# octanis_v0_1.net
KiCad netlist of a schematic drawn in EAGLE
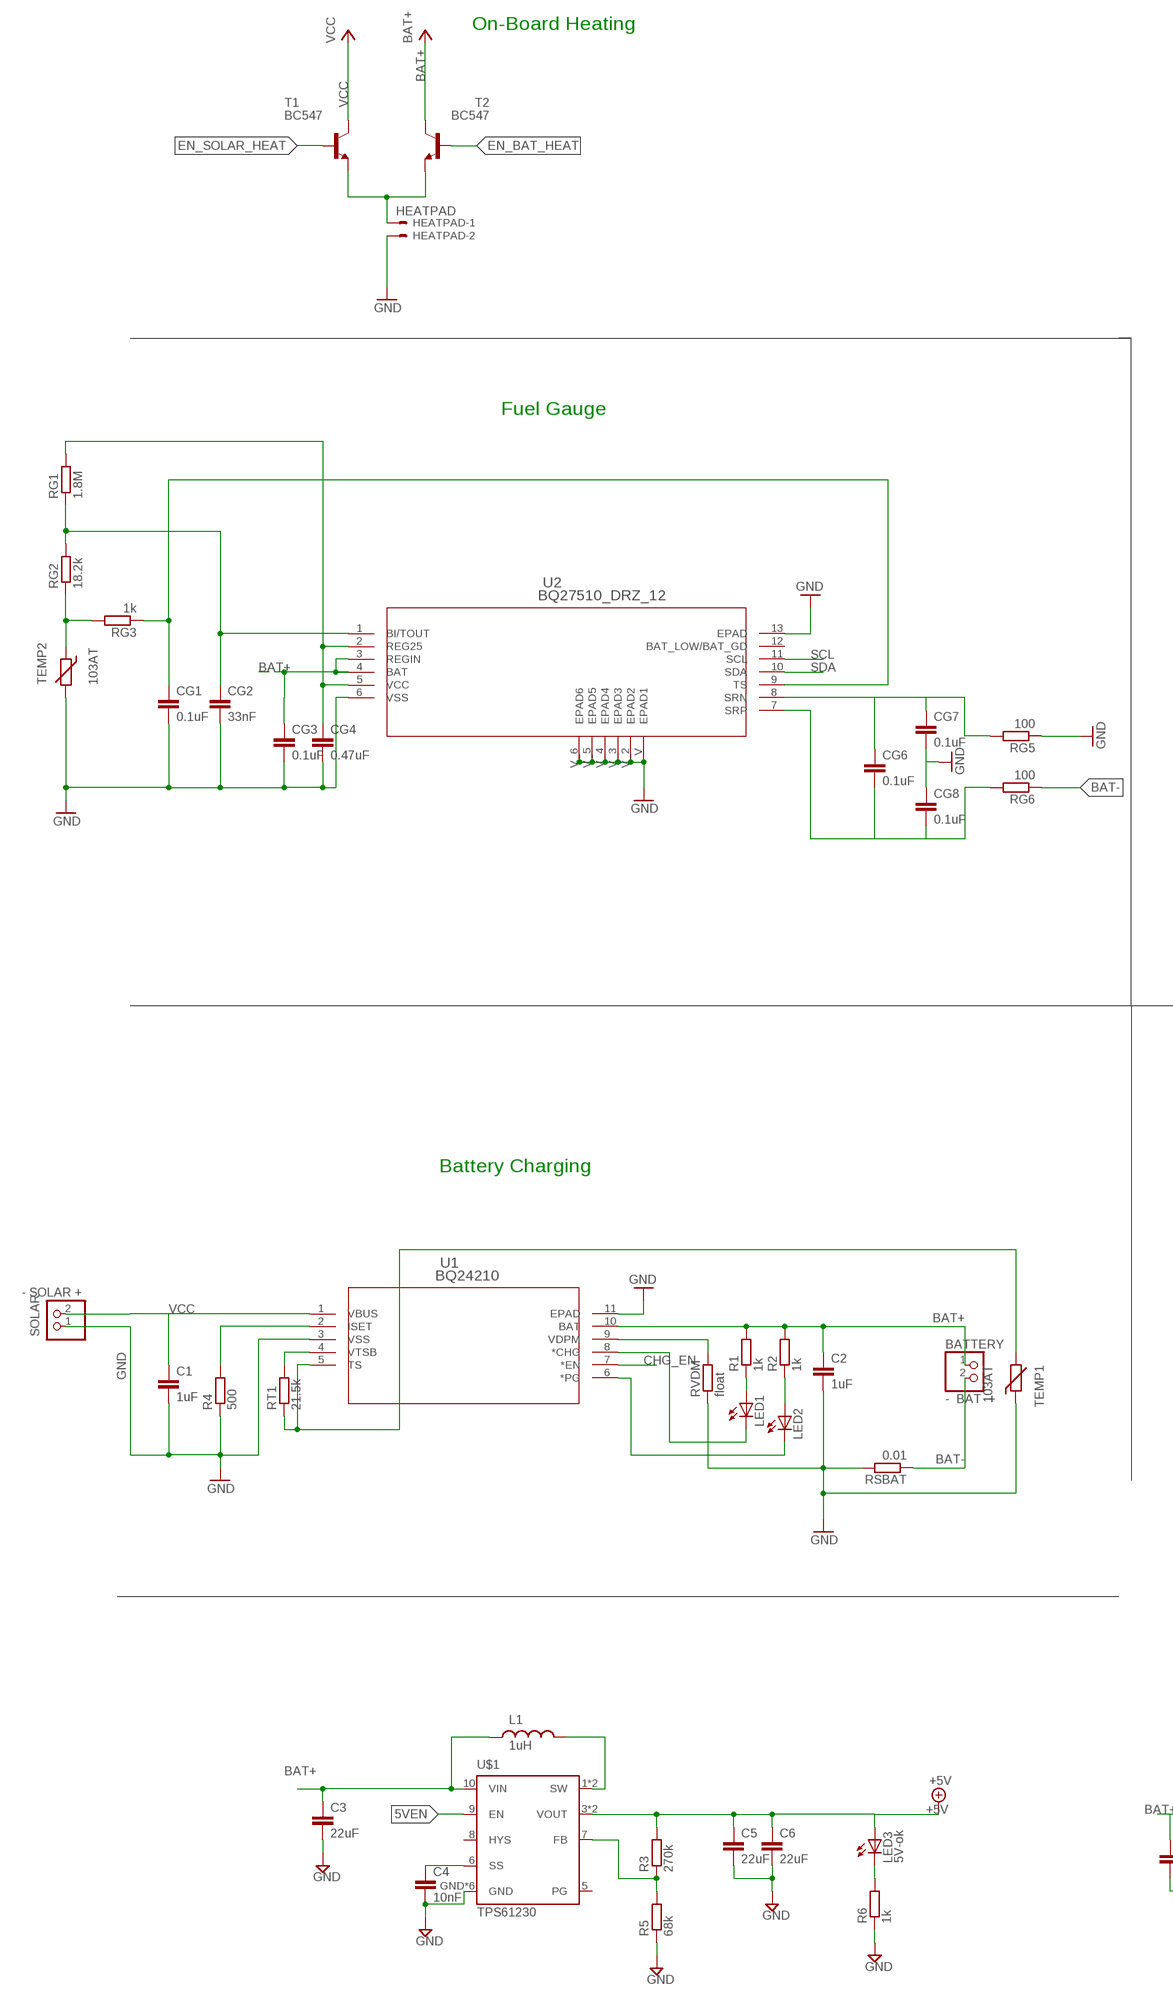
[diagram p0: schematic, sheet 1, part 1 of 3]
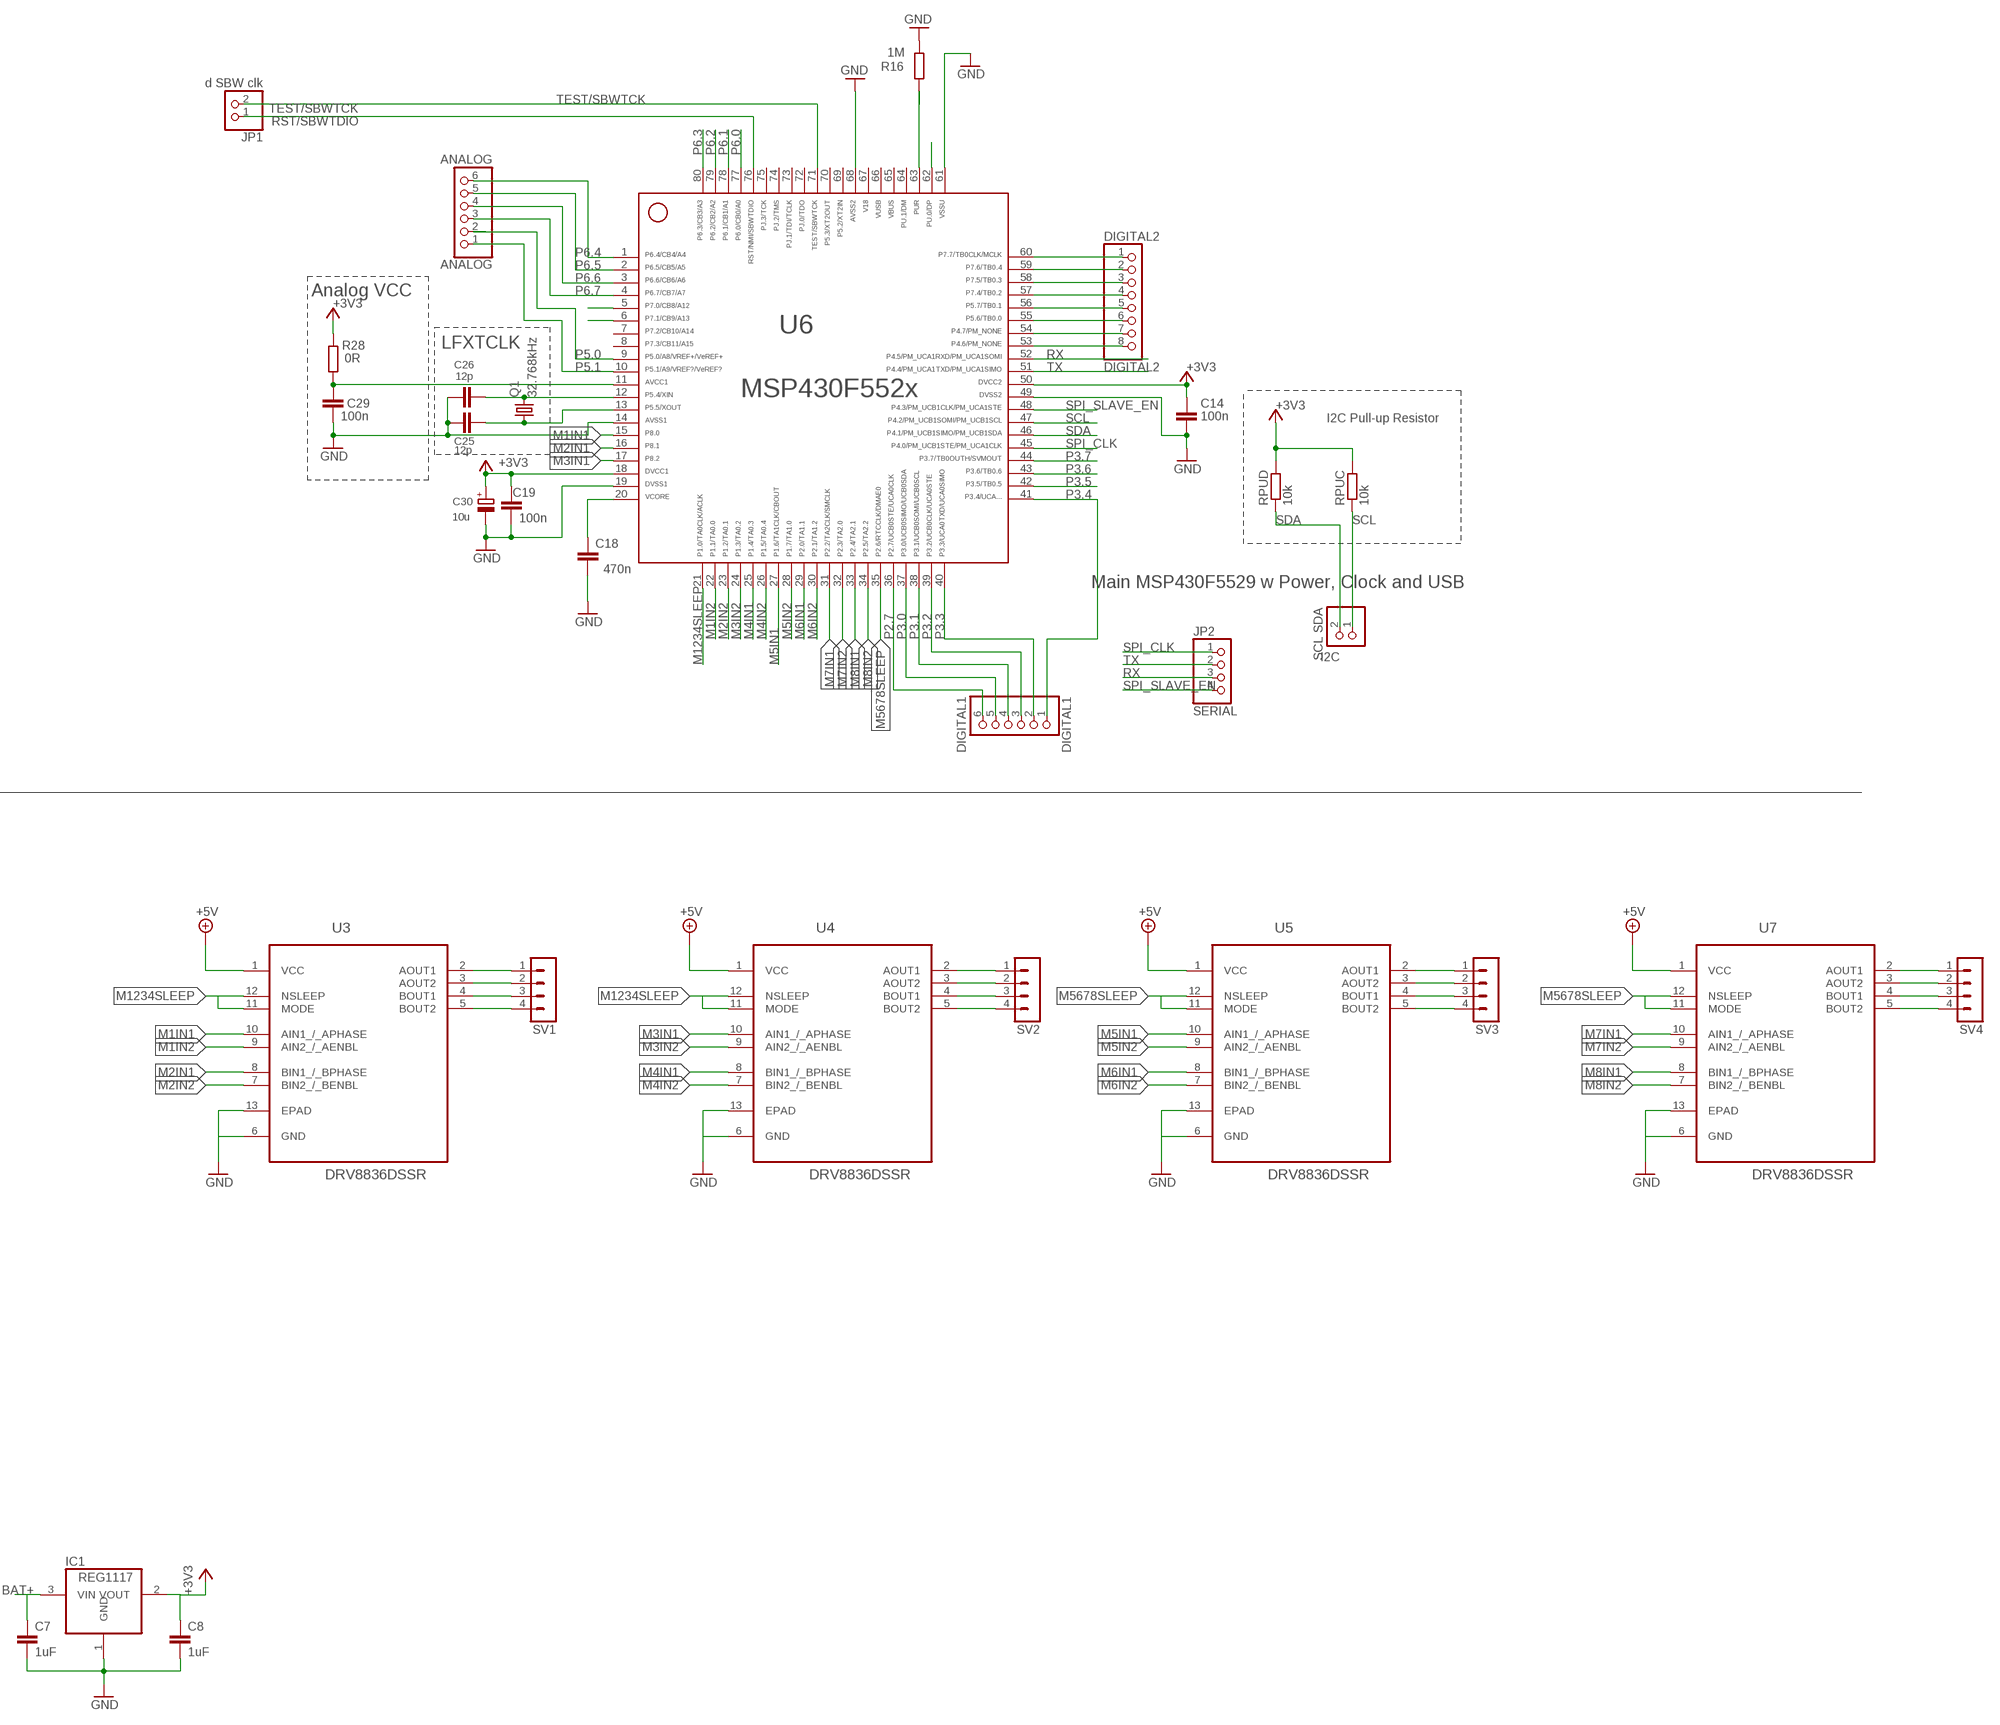
[diagram p1: schematic, sheet 1, part 2 of 3]
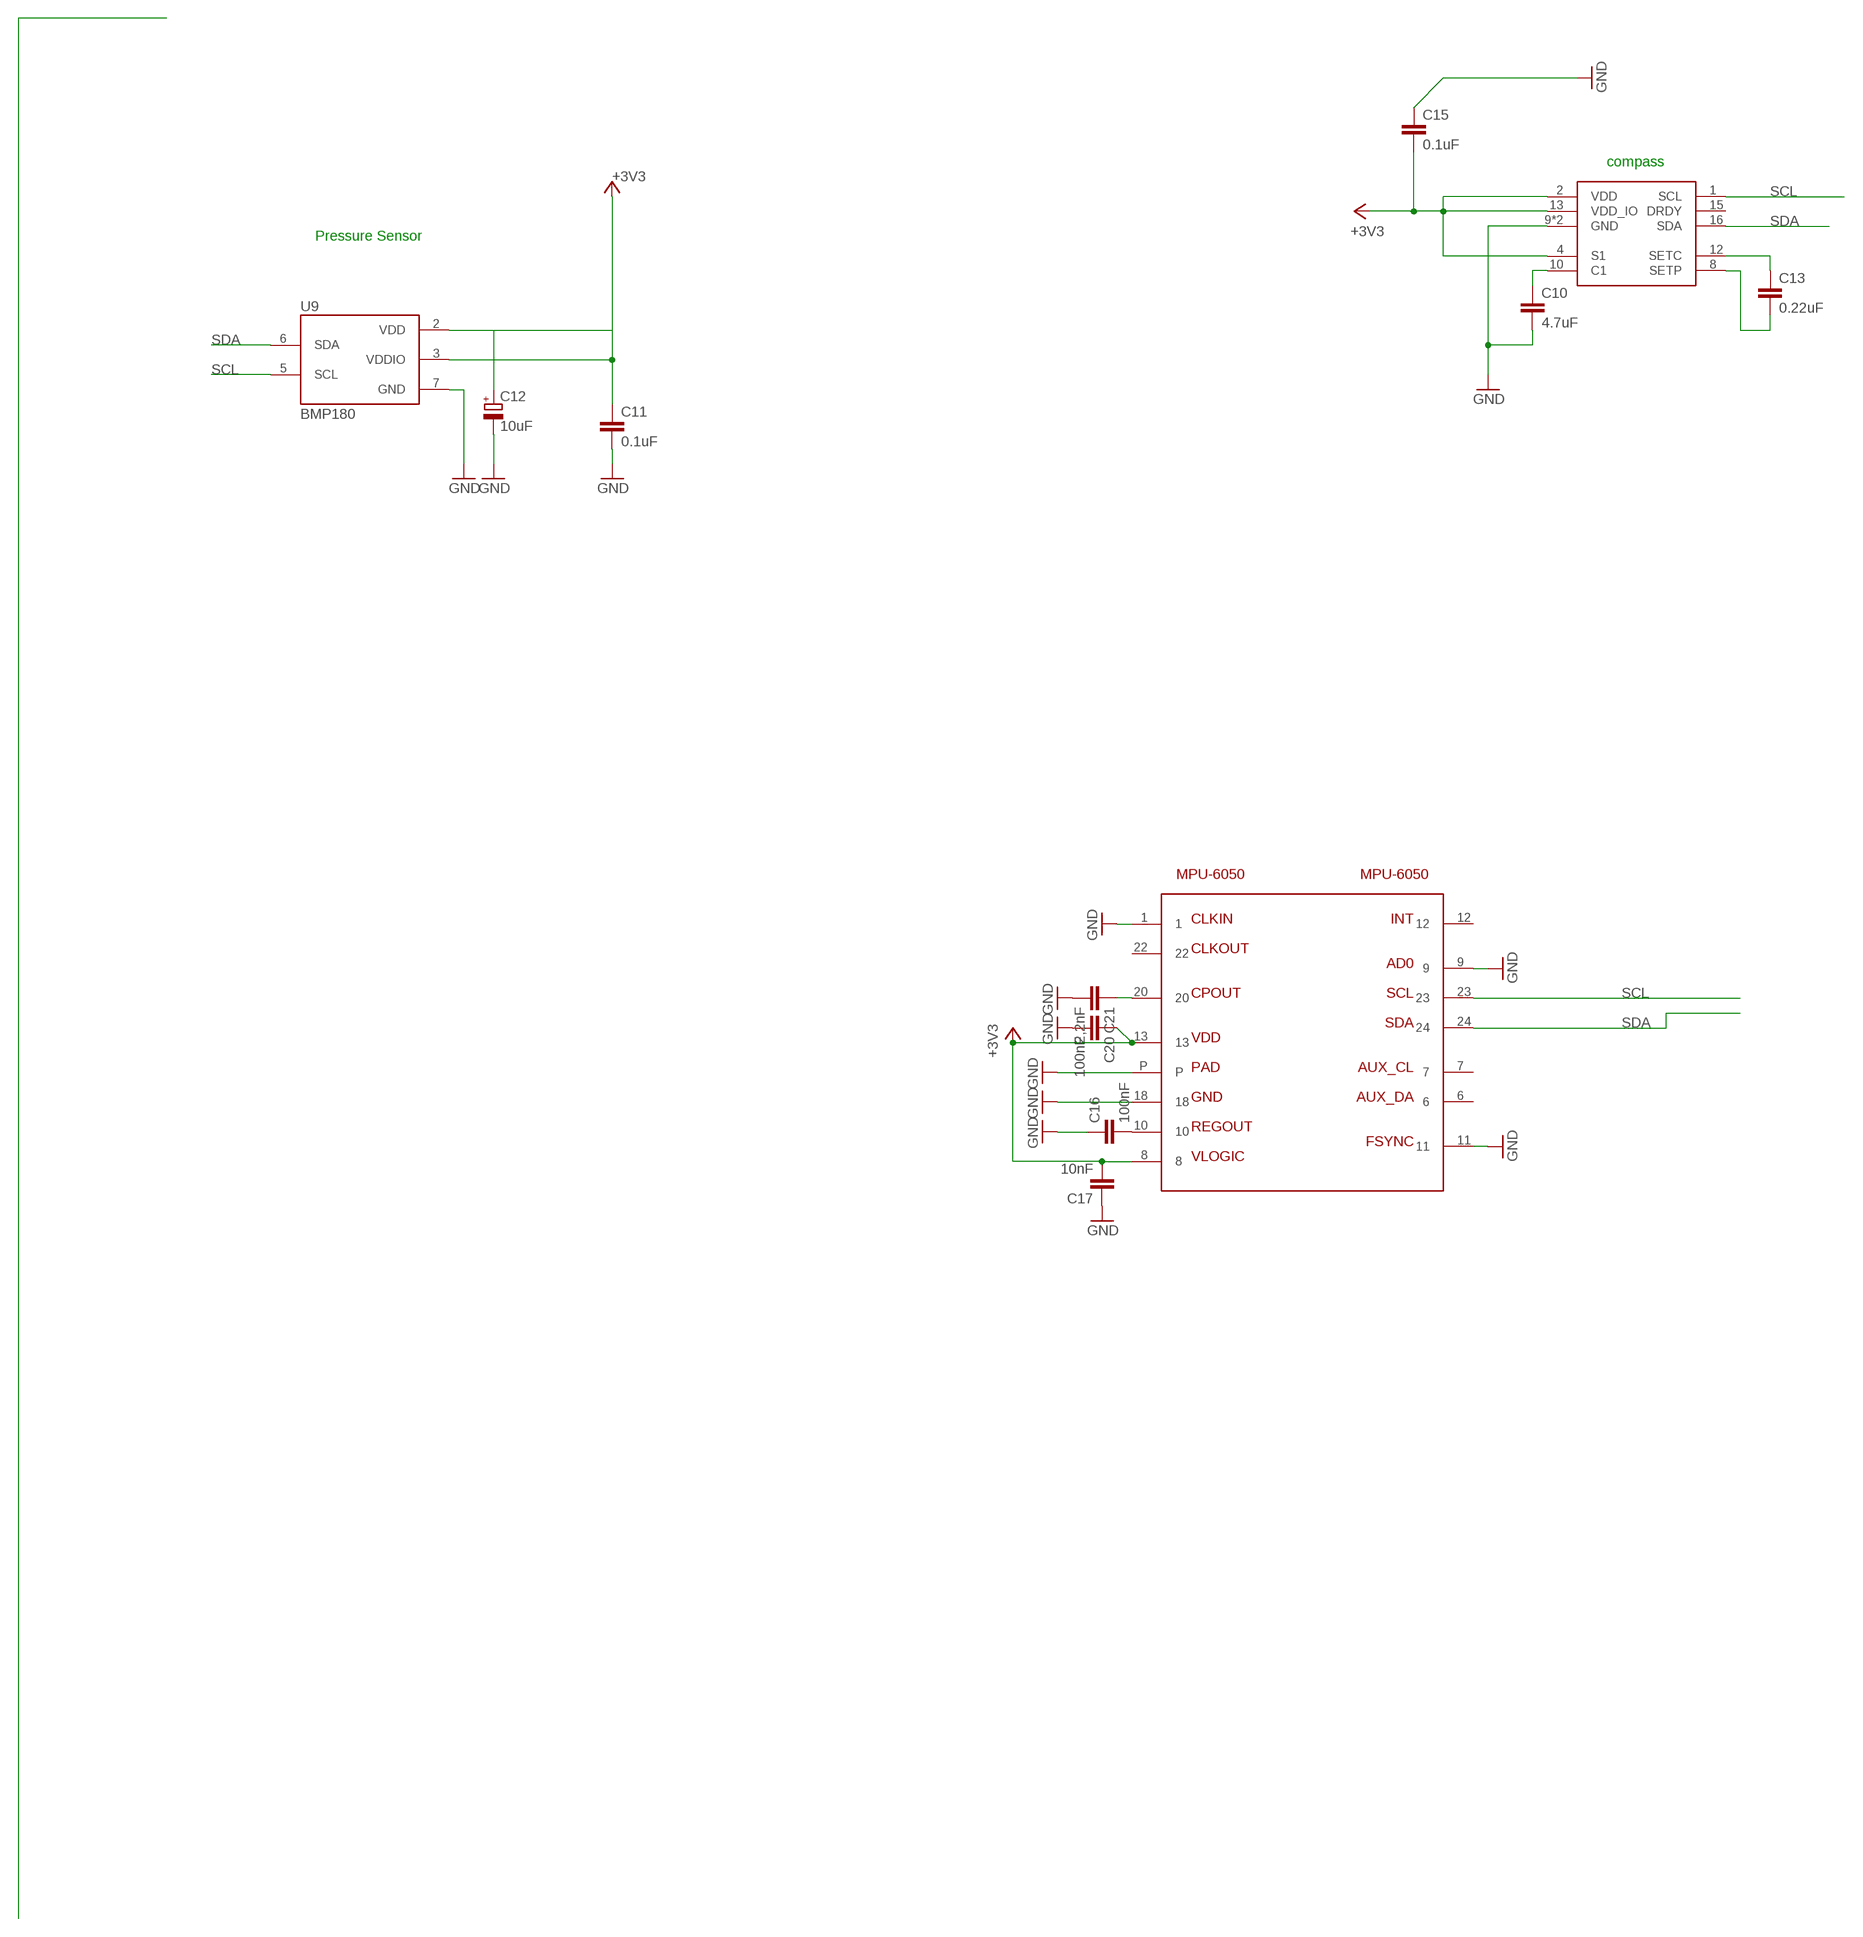
[diagram p2: schematic, sheet 1, part 3 of 3]

(export (version "E")
  (design (tool "Eeschema 10.0.6"))
  (components
    (comp (ref "ANALOG")
      (value "ANALOG")
      (footprint "eagle-import:1X06")
      (libsource (lib "eagle-import") (part "PINHD-1X6"))
    )
    (comp (ref "BATTERY")
      (value "- BAT +")
      (footprint "eagle-import:1X02")
      (libsource (lib "eagle-import") (part "PINHD-1X2"))
    )
    (comp (ref "C1")
      (value "1uF")
      (footprint "eagle-import:C1206")
      (libsource (lib "eagle-import") (part "C-EUC1206"))
    )
    (comp (ref "C2")
      (value "1uF")
      (footprint "eagle-import:C1206")
      (libsource (lib "eagle-import") (part "C-EUC1206"))
    )
    (comp (ref "C3")
      (value "22uF")
      (footprint "eagle-import:C0603")
      (libsource (lib "eagle-import") (part "C-EUC0603"))
    )
    (comp (ref "C4")
      (value "10nF")
      (footprint "eagle-import:C0603")
      (libsource (lib "eagle-import") (part "C-EUC0603"))
    )
    (comp (ref "C5")
      (value "22uF")
      (footprint "eagle-import:C0603")
      (libsource (lib "eagle-import") (part "C-EUC0603"))
    )
    (comp (ref "C6")
      (value "22uF")
      (footprint "eagle-import:C0603")
      (libsource (lib "eagle-import") (part "C-EUC0603"))
    )
    (comp (ref "C7")
      (value "1uF")
      (footprint "eagle-import:C0603")
      (libsource (lib "eagle-import") (part "C-EUC0603"))
    )
    (comp (ref "C8")
      (value "1uF")
      (footprint "eagle-import:C0603")
      (libsource (lib "eagle-import") (part "C-EUC0603"))
    )
    (comp (ref "C10")
      (value "4.7uF")
      (footprint "eagle-import:C0603")
      (libsource (lib "eagle-import") (part "C-EUC0603"))
    )
    (comp (ref "C11")
      (value "0.1uF")
      (footprint "eagle-import:C0603")
      (libsource (lib "eagle-import") (part "C-EUC0603"))
    )
    (comp (ref "C12")
      (value "10uF")
      (footprint "eagle-import:A_3216-18R")
      (libsource (lib "eagle-import") (part "resistor_CPOL-EUA/3216-18R"))
    )
    (comp (ref "C13")
      (value "0.22uF")
      (footprint "eagle-import:C0603")
      (libsource (lib "eagle-import") (part "C-EUC0603"))
    )
    (comp (ref "C14")
      (value "100n")
      (footprint "eagle-import:C0603")
      (libsource (lib "eagle-import") (part "C-EUC0603"))
    )
    (comp (ref "C15")
      (value "0.1uF")
      (footprint "eagle-import:C0603")
      (libsource (lib "eagle-import") (part "C-EUC0603"))
    )
    (comp (ref "C16")
      (value "100nF")
      (footprint "eagle-import:C0603")
      (libsource (lib "eagle-import") (part "C-EUC0603"))
    )
    (comp (ref "C17")
      (value "10nF")
      (footprint "eagle-import:C0603")
      (libsource (lib "eagle-import") (part "C-EUC0603"))
    )
    (comp (ref "C18")
      (value "470n")
      (footprint "eagle-import:C0603")
      (libsource (lib "eagle-import") (part "C-EUC0603"))
    )
    (comp (ref "C19")
      (value "100n")
      (footprint "eagle-import:C0603")
      (libsource (lib "eagle-import") (part "C-EUC0603"))
    )
    (comp (ref "C20")
      (value "100nF")
      (footprint "eagle-import:C0603")
      (libsource (lib "eagle-import") (part "C-EUC0603"))
    )
    (comp (ref "C21")
      (value "2,2nF")
      (footprint "eagle-import:C0603")
      (libsource (lib "eagle-import") (part "C-EUC0603"))
    )
    (comp (ref "C25")
      (value "12p")
      (footprint "eagle-import:C0603")
      (libsource (lib "eagle-import") (part "C-EUC0603"))
    )
    (comp (ref "C26")
      (value "12p")
      (footprint "eagle-import:C0603")
      (libsource (lib "eagle-import") (part "C-EUC0603"))
    )
    (comp (ref "C29")
      (value "100n")
      (footprint "eagle-import:C0603")
      (libsource (lib "eagle-import") (part "C-EUC0603"))
    )
    (comp (ref "C30")
      (value "10u")
      (footprint "eagle-import:A_3216-18R")
      (libsource (lib "eagle-import") (part "CPOL-EUA/3216-18R"))
    )
    (comp (ref "CG1")
      (value "0.1uF")
      (footprint "eagle-import:C0603")
      (libsource (lib "eagle-import") (part "C-EUC0603"))
    )
    (comp (ref "CG2")
      (value "33nF")
      (footprint "eagle-import:C0603")
      (libsource (lib "eagle-import") (part "C-EUC0603"))
    )
    (comp (ref "CG3")
      (value "0.1uF")
      (footprint "eagle-import:C0603")
      (libsource (lib "eagle-import") (part "C-EUC0603"))
    )
    (comp (ref "CG4")
      (value "0.47uF")
      (footprint "eagle-import:C0603")
      (libsource (lib "eagle-import") (part "C-EUC0603"))
    )
    (comp (ref "CG6")
      (value "0.1uF")
      (footprint "eagle-import:C0603")
      (libsource (lib "eagle-import") (part "C-EUC0603"))
    )
    (comp (ref "CG7")
      (value "0.1uF")
      (footprint "eagle-import:C0603")
      (libsource (lib "eagle-import") (part "C-EUC0603"))
    )
    (comp (ref "CG8")
      (value "0.1uF")
      (footprint "eagle-import:C0603")
      (libsource (lib "eagle-import") (part "C-EUC0603"))
    )
    (comp (ref "COMPASS")
      (value "HMC5883L")
      (footprint "eagle-import:LPCC16")
      (libsource (lib "eagle-import") (part "HMC5883L"))
    )
    (comp (ref "DIGITAL1")
      (value "DIGITAL1")
      (footprint "eagle-import:1X06")
      (libsource (lib "eagle-import") (part "PINHD-1X6"))
    )
    (comp (ref "DIGITAL2")
      (value "DIGITAL2")
      (footprint "eagle-import:1X08")
      (libsource (lib "eagle-import") (part "PINHD-1X8"))
    )
    (comp (ref "HEATPAD")
      (value "HEATPAD")
      (footprint "eagle-import:22-23-2021")
      (fields (field (name "MF") "MOLEX") (field (name "MPN") "22-23-2021"))
      (libsource (lib "eagle-import") (part "22-23-2021"))
    )
    (comp (ref "I2C")
      (value "SCL SDA")
      (footprint "eagle-import:1X02")
      (libsource (lib "eagle-import") (part "PINHD-1X2"))
    )
    (comp (ref "IC1")
      (value "REG1117")
      (footprint "eagle-import:SOT223")
      (libsource (lib "eagle-import") (part "REG1117"))
    )
    (comp (ref "JP1")
      (value "d SBW clk")
      (footprint "eagle-import:1X02")
      (libsource (lib "eagle-import") (part "PINHD-1X2"))
    )
    (comp (ref "JP2")
      (value "SERIAL")
      (footprint "eagle-import:1X04")
      (libsource (lib "eagle-import") (part "PINHD-1X4"))
    )
    (comp (ref "L1")
      (value "1uH")
      (footprint "eagle-import:XFL4020")
      (libsource (lib "eagle-import") (part "XFL4020"))
    )
    (comp (ref "LED1")
      (value "LEDCHIP-LED0603")
      (footprint "eagle-import:CHIP-LED0603")
      (libsource (lib "eagle-import") (part "led_LEDCHIP-LED0603"))
    )
    (comp (ref "LED2")
      (value "LEDCHIP-LED0603")
      (footprint "eagle-import:CHIP-LED0603")
      (libsource (lib "eagle-import") (part "led_LEDCHIP-LED0603"))
    )
    (comp (ref "LED3")
      (value "5V-ok")
      (footprint "eagle-import:CHIPLED_0603")
      (libsource (lib "eagle-import") (part "LEDCHIPLED_0603"))
    )
    (comp (ref "MPU-6050")
      (value "MPU-6050")
      (footprint "eagle-import:QFN24")
      (libsource (lib "eagle-import") (part "MPU-6050"))
    )
    (comp (ref "Q1")
      (value "32.768kHz")
      (footprint "eagle-import:FC-12M")
      (libsource (lib "eagle-import") (part "FC-12M"))
    )
    (comp (ref "R1")
      (value "1k")
      (footprint "eagle-import:R0603")
      (libsource (lib "eagle-import") (part "R-EU_R0603"))
    )
    (comp (ref "R2")
      (value "1k")
      (footprint "eagle-import:R0603")
      (libsource (lib "eagle-import") (part "R-EU_R0603"))
    )
    (comp (ref "R3")
      (value "270k")
      (footprint "eagle-import:R0603")
      (libsource (lib "eagle-import") (part "R-EU_R0603"))
    )
    (comp (ref "R4")
      (value "500")
      (footprint "eagle-import:R1206")
      (libsource (lib "eagle-import") (part "resistor_R-EU_R1206"))
    )
    (comp (ref "R5")
      (value "68k")
      (footprint "eagle-import:R0603")
      (libsource (lib "eagle-import") (part "R-EU_R0603"))
    )
    (comp (ref "R6")
      (value "1k")
      (footprint "eagle-import:R0603")
      (libsource (lib "eagle-import") (part "R-EU_R0603"))
    )
    (comp (ref "R16")
      (value "1M")
      (footprint "eagle-import:R0603")
      (libsource (lib "eagle-import") (part "R-EU_R0603"))
    )
    (comp (ref "R28")
      (value "0R")
      (footprint "eagle-import:R0603")
      (libsource (lib "eagle-import") (part "R-EU_R0603"))
    )
    (comp (ref "RG1")
      (value "1.8M")
      (footprint "eagle-import:R0603")
      (libsource (lib "eagle-import") (part "R-EU_R0603"))
    )
    (comp (ref "RG2")
      (value "18.2k")
      (footprint "eagle-import:R0603")
      (libsource (lib "eagle-import") (part "R-EU_R0603"))
    )
    (comp (ref "RG3")
      (value "1k")
      (footprint "eagle-import:R0603")
      (libsource (lib "eagle-import") (part "R-EU_R0603"))
    )
    (comp (ref "RG5")
      (value "100")
      (footprint "eagle-import:R0603")
      (libsource (lib "eagle-import") (part "R-EU_R0603"))
    )
    (comp (ref "RG6")
      (value "100")
      (footprint "eagle-import:R0603")
      (libsource (lib "eagle-import") (part "R-EU_R0603"))
    )
    (comp (ref "RPUC")
      (value "10k")
      (footprint "eagle-import:R0603")
      (libsource (lib "eagle-import") (part "R-EU_R0603"))
    )
    (comp (ref "RPUD")
      (value "10k")
      (footprint "eagle-import:R0603")
      (libsource (lib "eagle-import") (part "R-EU_R0603"))
    )
    (comp (ref "RSBAT")
      (value "0.01")
      (footprint "eagle-import:R1206")
      (libsource (lib "eagle-import") (part "resistor_R-EU_R1206"))
    )
    (comp (ref "RT1")
      (value "21.5k")
      (footprint "eagle-import:R1206")
      (libsource (lib "eagle-import") (part "resistor_R-EU_R1206"))
    )
    (comp (ref "RVDM")
      (value "float")
      (footprint "eagle-import:R1206")
      (libsource (lib "eagle-import") (part "resistor_R-EU_R1206"))
    )
    (comp (ref "SOLAR")
      (value "- SOLAR +")
      (footprint "eagle-import:1X02")
      (libsource (lib "eagle-import") (part "PINHD-1X2"))
    )
    (comp (ref "SV1")
      (value "MA04-1")
      (footprint "eagle-import:MA04-1")
      (libsource (lib "eagle-import") (part "MA04-1"))
    )
    (comp (ref "SV2")
      (value "MA04-1")
      (footprint "eagle-import:MA04-1")
      (libsource (lib "eagle-import") (part "MA04-1"))
    )
    (comp (ref "SV3")
      (value "MA04-1")
      (footprint "eagle-import:MA04-1")
      (libsource (lib "eagle-import") (part "MA04-1"))
    )
    (comp (ref "SV4")
      (value "MA04-1")
      (footprint "eagle-import:MA04-1")
      (libsource (lib "eagle-import") (part "MA04-1"))
    )
    (comp (ref "T1")
      (value "BC547")
      (footprint "eagle-import:TO92")
      (libsource (lib "eagle-import") (part "BC547"))
    )
    (comp (ref "T2")
      (value "BC547")
      (footprint "eagle-import:TO92")
      (libsource (lib "eagle-import") (part "BC547"))
    )
    (comp (ref "TEMP1")
      (value "103AT")
      (footprint "eagle-import:RS-2,5")
      (libsource (lib "eagle-import") (part "THERMISTOR-2,5"))
    )
    (comp (ref "TEMP2")
      (value "103AT")
      (footprint "eagle-import:RS-2,5")
      (libsource (lib "eagle-import") (part "THERMISTOR-2,5"))
    )
    (comp (ref "U$1")
      (value "TPS61230")
      (footprint "eagle-import:DRC-S-PVSON-N11")
      (libsource (lib "eagle-import") (part "TPS61230"))
    )
    (comp (ref "U1")
      (value "BQ24210")
      (footprint "eagle-import:DQC10_P84X2P4")
      (fields (field (name "MANUFACTURER") "Texas Instruments"))
      (libsource (lib "eagle-import") (part "BQ24210_DQC_10"))
    )
    (comp (ref "U2")
      (value "BQ27510_DRZ_12")
      (footprint "eagle-import:DRZ12_1P95X2P45")
      (fields
        (field (name "GENERIC_PART_NUMBER") "BQ27510")
        (field (name "MANUFACTURER") "Texas Instruments")
      )
      (libsource (lib "eagle-import") (part "BQ27510_DRZ_12"))
    )
    (comp (ref "U3")
      (value "DRV8836DSSR")
      (footprint "eagle-import:SON50P200X300X80-13N")
      (fields (field (name "MPN") "DRV8836DSSR "))
      (libsource (lib "eagle-import") (part "DRV8836DSSR"))
    )
    (comp (ref "U4")
      (value "DRV8836DSSR")
      (footprint "eagle-import:SON50P200X300X80-13N")
      (fields (field (name "MPN") "DRV8836DSSR "))
      (libsource (lib "eagle-import") (part "DRV8836DSSR"))
    )
    (comp (ref "U5")
      (value "DRV8836DSSR")
      (footprint "eagle-import:SON50P200X300X80-13N")
      (fields (field (name "MPN") "DRV8836DSSR "))
      (libsource (lib "eagle-import") (part "DRV8836DSSR"))
    )
    (comp (ref "U6")
      (value "MSP430F5529IPNR")
      (footprint "eagle-import:PN80")
      (libsource (lib "eagle-import") (part "F552X---PN80"))
    )
    (comp (ref "U7")
      (value "DRV8836DSSR")
      (footprint "eagle-import:SON50P200X300X80-13N")
      (fields (field (name "MPN") "DRV8836DSSR "))
      (libsource (lib "eagle-import") (part "DRV8836DSSR"))
    )
    (comp (ref "U9")
      (value "BMP180")
      (footprint "eagle-import:BMP180")
      (libsource (lib "eagle-import") (part "BMP180"))
    )
  )
  (nets
    (net (code "1") (name "+3V3") (class "Default")
      (node (ref "C11") (pin "1") (pinfunction "1_1") (pintype "passive"))
      (node (ref "C12") (pin "+") (pinfunction "+_+") (pintype "passive"))
      (node (ref "C14") (pin "1") (pinfunction "1_1") (pintype "passive"))
      (node (ref "C15") (pin "2") (pinfunction "2_2") (pintype "passive"))
      (node (ref "C17") (pin "2") (pinfunction "2_2") (pintype "passive"))
      (node (ref "C19") (pin "2") (pinfunction "2_2") (pintype "passive"))
      (node (ref "C20") (pin "1") (pinfunction "1_1") (pintype "passive"))
      (node (ref "C30") (pin "+") (pinfunction "+_+") (pintype "passive"))
      (node (ref "C8") (pin "1") (pinfunction "1_1") (pintype "passive"))
      (node (ref "COMPASS") (pin "13") (pinfunction "VDD_IO_13") (pintype "power_in"))
      (node (ref "COMPASS") (pin "2") (pinfunction "VDD_2") (pintype "power_in"))
      (node (ref "COMPASS") (pin "4") (pinfunction "S1_4") (pintype "power_in"))
      (node (ref "IC1") (pin "2") (pinfunction "VOUT_2") (pintype "output"))
      (node (ref "MPU-6050") (pin "13") (pinfunction "13_13") (pintype "bidirectional"))
      (node (ref "MPU-6050") (pin "8") (pinfunction "8_8") (pintype "bidirectional"))
      (node (ref "R28") (pin "2") (pinfunction "2_2") (pintype "passive"))
      (node (ref "RPUC") (pin "2") (pinfunction "2_2") (pintype "passive"))
      (node (ref "RPUD") (pin "2") (pinfunction "2_2") (pintype "passive"))
      (node (ref "U6") (pin "18") (pinfunction "18_18") (pintype "power_in"))
      (node (ref "U6") (pin "50") (pinfunction "50_50") (pintype "power_in"))
      (node (ref "U9") (pin "2") (pinfunction "VDD_2") (pintype "power_in"))
      (node (ref "U9") (pin "3") (pinfunction "VDDIO_3") (pintype "power_in"))
    )
    (net (code "2") (name "+5V") (class "Default")
      (node (ref "C5") (pin "1") (pinfunction "1_1") (pintype "passive"))
      (node (ref "C6") (pin "1") (pinfunction "1_1") (pintype "passive"))
      (node (ref "LED3") (pin "A") (pinfunction "A_A") (pintype "passive"))
      (node (ref "R3") (pin "2") (pinfunction "2_2") (pintype "passive"))
      (node (ref "U$1") (pin "3") (pinfunction "VOUT_3") (pintype "passive"))
      (node (ref "U$1") (pin "4") (pinfunction "VOUT_4") (pintype "passive"))
      (node (ref "U3") (pin "1") (pinfunction "VCC_1") (pintype "power_in"))
      (node (ref "U4") (pin "1") (pinfunction "VCC_1") (pintype "power_in"))
      (node (ref "U5") (pin "1") (pinfunction "VCC_1") (pintype "power_in"))
      (node (ref "U7") (pin "1") (pinfunction "VCC_1") (pintype "power_in"))
    )
    (net (code "3") (name "/65") (class "Default")
      (node (ref "U6") (pin "65") (pinfunction "65_65") (pintype "power_in"))
    )
    (net (code "4") (name "/66") (class "Default")
      (node (ref "U6") (pin "66") (pinfunction "66_66") (pintype "power_in"))
    )
    (net (code "5") (name "/67") (class "Default")
      (node (ref "U6") (pin "67") (pinfunction "67_67") (pintype "power_in"))
    )
    (net (code "6") (name "/CHG_EN") (class "Default")
      (node (ref "U1") (pin "7") (pinfunction "*EN_7") (pintype "input"))
      (node (ref "U6") (pin "5") (pinfunction "5_5") (pintype "bidirectional"))
    )
    (net (code "7") (name "/P2.7") (class "Default")
      (node (ref "DIGITAL1") (pin "6") (pinfunction "6_6") (pintype "passive"))
      (node (ref "U6") (pin "36") (pinfunction "36_36") (pintype "bidirectional"))
    )
    (net (code "8") (name "/P3.0") (class "Default")
      (node (ref "DIGITAL1") (pin "5") (pinfunction "5_5") (pintype "passive"))
      (node (ref "U6") (pin "37") (pinfunction "37_37") (pintype "bidirectional"))
    )
    (net (code "9") (name "/P3.1") (class "Default")
      (node (ref "DIGITAL1") (pin "4") (pinfunction "4_4") (pintype "passive"))
      (node (ref "U6") (pin "38") (pinfunction "38_38") (pintype "bidirectional"))
    )
    (net (code "10") (name "/P3.2") (class "Default")
      (node (ref "DIGITAL1") (pin "3") (pinfunction "3_3") (pintype "passive"))
      (node (ref "U6") (pin "39") (pinfunction "39_39") (pintype "bidirectional"))
    )
    (net (code "11") (name "/P3.3") (class "Default")
      (node (ref "DIGITAL1") (pin "2") (pinfunction "2_2") (pintype "passive"))
      (node (ref "U6") (pin "40") (pinfunction "40_40") (pintype "bidirectional"))
    )
    (net (code "12") (name "/P3.4") (class "Default")
      (node (ref "DIGITAL1") (pin "1") (pinfunction "1_1") (pintype "passive"))
      (node (ref "U6") (pin "41") (pinfunction "41_41") (pintype "bidirectional"))
    )
    (net (code "13") (name "/P3.5") (class "Default")
      (node (ref "U6") (pin "42") (pinfunction "42_42") (pintype "bidirectional"))
    )
    (net (code "14") (name "/P3.6") (class "Default")
      (node (ref "U6") (pin "43") (pinfunction "43_43") (pintype "bidirectional"))
    )
    (net (code "15") (name "/P3.7") (class "Default")
      (node (ref "U6") (pin "44") (pinfunction "44_44") (pintype "bidirectional"))
    )
    (net (code "16") (name "/P5.0") (class "Default")
      (node (ref "ANALOG") (pin "2") (pinfunction "2_2") (pintype "passive"))
      (node (ref "U6") (pin "9") (pinfunction "9_9") (pintype "bidirectional"))
    )
    (net (code "17") (name "/P5.1") (class "Default")
      (node (ref "ANALOG") (pin "1") (pinfunction "1_1") (pintype "passive"))
      (node (ref "U6") (pin "10") (pinfunction "10_10") (pintype "bidirectional"))
    )
    (net (code "18") (name "/P6.0") (class "Default")
      (node (ref "U6") (pin "77") (pinfunction "77_77") (pintype "bidirectional"))
    )
    (net (code "19") (name "/P6.1") (class "Default")
      (node (ref "U6") (pin "78") (pinfunction "78_78") (pintype "bidirectional"))
    )
    (net (code "20") (name "/P6.2") (class "Default")
      (node (ref "U6") (pin "79") (pinfunction "79_79") (pintype "bidirectional"))
    )
    (net (code "21") (name "/P6.3") (class "Default")
      (node (ref "U6") (pin "80") (pinfunction "80_80") (pintype "bidirectional"))
    )
    (net (code "22") (name "/P6.4") (class "Default")
      (node (ref "ANALOG") (pin "6") (pinfunction "6_6") (pintype "passive"))
      (node (ref "U6") (pin "1") (pinfunction "1_1") (pintype "bidirectional"))
    )
    (net (code "23") (name "/P6.5") (class "Default")
      (node (ref "ANALOG") (pin "5") (pinfunction "5_5") (pintype "passive"))
      (node (ref "U6") (pin "2") (pinfunction "2_2") (pintype "bidirectional"))
    )
    (net (code "24") (name "/P6.6") (class "Default")
      (node (ref "ANALOG") (pin "4") (pinfunction "4_4") (pintype "passive"))
      (node (ref "U6") (pin "3") (pinfunction "3_3") (pintype "bidirectional"))
    )
    (net (code "25") (name "/P6.7") (class "Default")
      (node (ref "ANALOG") (pin "3") (pinfunction "3_3") (pintype "passive"))
      (node (ref "U6") (pin "4") (pinfunction "4_4") (pintype "bidirectional"))
    )
    (net (code "26") (name "/PG") (class "Default")
      (node (ref "U$1") (pin "5") (pinfunction "PG_5") (pintype "power_in"))
    )
    (net (code "27") (name "/RST{slash}SBWTDIO") (class "Default")
      (node (ref "JP1") (pin "1") (pinfunction "1_1") (pintype "passive"))
      (node (ref "U6") (pin "76") (pinfunction "76_76") (pintype "bidirectional"))
    )
    (net (code "28") (name "/RX") (class "Default")
      (node (ref "JP2") (pin "3") (pinfunction "3_3") (pintype "passive"))
      (node (ref "U6") (pin "52") (pinfunction "52_52") (pintype "bidirectional"))
    )
    (net (code "29") (name "/SCL") (class "Default")
      (node (ref "COMPASS") (pin "1") (pinfunction "SCL_1") (pintype "input"))
      (node (ref "I2C") (pin "1") (pinfunction "1_1") (pintype "passive"))
      (node (ref "MPU-6050") (pin "23") (pinfunction "23_23") (pintype "bidirectional"))
      (node (ref "RPUC") (pin "1") (pinfunction "1_1") (pintype "passive"))
      (node (ref "U2") (pin "11") (pinfunction "SCL_11") (pintype "input"))
      (node (ref "U6") (pin "47") (pinfunction "47_47") (pintype "bidirectional"))
      (node (ref "U9") (pin "5") (pinfunction "SCL_5") (pintype "input"))
    )
    (net (code "30") (name "/SDA") (class "Default")
      (node (ref "COMPASS") (pin "16") (pinfunction "SDA_16") (pintype "input"))
      (node (ref "I2C") (pin "2") (pinfunction "2_2") (pintype "passive"))
      (node (ref "MPU-6050") (pin "24") (pinfunction "24_24") (pintype "bidirectional"))
      (node (ref "RPUD") (pin "1") (pinfunction "1_1") (pintype "passive"))
      (node (ref "U2") (pin "10") (pinfunction "SDA_10") (pintype "bidirectional"))
      (node (ref "U6") (pin "46") (pinfunction "46_46") (pintype "bidirectional"))
      (node (ref "U9") (pin "6") (pinfunction "SDA_6") (pintype "bidirectional"))
    )
    (net (code "31") (name "/SPI_CLK") (class "Default")
      (node (ref "JP2") (pin "1") (pinfunction "1_1") (pintype "passive"))
      (node (ref "U6") (pin "45") (pinfunction "45_45") (pintype "bidirectional"))
    )
    (net (code "32") (name "/SPI_SLAVE_EN") (class "Default")
      (node (ref "JP2") (pin "4") (pinfunction "4_4") (pintype "passive"))
      (node (ref "U6") (pin "48") (pinfunction "48_48") (pintype "bidirectional"))
    )
    (net (code "33") (name "/TEST{slash}SBWTCK") (class "Default")
      (node (ref "JP1") (pin "2") (pinfunction "2_2") (pintype "passive"))
      (node (ref "U6") (pin "71") (pinfunction "71_71") (pintype "input"))
    )
    (net (code "34") (name "/TX") (class "Default")
      (node (ref "JP2") (pin "2") (pinfunction "2_2") (pintype "passive"))
      (node (ref "U6") (pin "51") (pinfunction "51_51") (pintype "bidirectional"))
    )
    (net (code "35") (name "5VEN") (class "Default")
      (node (ref "U$1") (pin "9") (pinfunction "EN_9") (pintype "input"))
      (node (ref "U6") (pin "6") (pinfunction "6_6") (pintype "bidirectional"))
    )
    (net (code "36") (name "BAT+") (class "Default")
      (node (ref "BATTERY") (pin "1") (pinfunction "1_1") (pintype "passive"))
      (node (ref "C2") (pin "1") (pinfunction "1_1") (pintype "passive"))
      (node (ref "C3") (pin "1") (pinfunction "1_1") (pintype "passive"))
      (node (ref "C7") (pin "1") (pinfunction "1_1") (pintype "passive"))
      (node (ref "CG3") (pin "1") (pinfunction "1_1") (pintype "passive"))
      (node (ref "IC1") (pin "3") (pinfunction "VIN_3") (pintype "input"))
      (node (ref "L1") (pin "P$1") (pinfunction "1_P$1") (pintype "passive"))
      (node (ref "R1") (pin "2") (pinfunction "2_2") (pintype "passive"))
      (node (ref "R2") (pin "2") (pinfunction "2_2") (pintype "passive"))
      (node (ref "T2") (pin "3") (pinfunction "C_3") (pintype "passive"))
      (node (ref "U$1") (pin "10") (pinfunction "VIN_10") (pintype "input"))
      (node (ref "U1") (pin "10") (pinfunction "BAT_10") (pintype "bidirectional"))
      (node (ref "U2") (pin "3") (pinfunction "REGIN_3") (pintype "power_in"))
      (node (ref "U2") (pin "4") (pinfunction "BAT_4") (pintype "input"))
    )
    (net (code "37") (name "BAT-") (class "Default")
      (node (ref "BATTERY") (pin "2") (pinfunction "2_2") (pintype "passive"))
      (node (ref "RG6") (pin "1") (pinfunction "1_1") (pintype "passive"))
      (node (ref "RSBAT") (pin "1") (pinfunction "1_1") (pintype "passive"))
    )
    (net (code "38") (name "EN_BAT_HEAT") (class "Default")
      (node (ref "T2") (pin "2") (pinfunction "B_2") (pintype "passive"))
    )
    (net (code "39") (name "EN_SOLAR_HEAT") (class "Default")
      (node (ref "T1") (pin "2") (pinfunction "B_2") (pintype "passive"))
    )
    (net (code "40") (name "GND") (class "Default")
      (node (ref "C1") (pin "2") (pinfunction "2_2") (pintype "passive"))
      (node (ref "C10") (pin "2") (pinfunction "2_2") (pintype "passive"))
      (node (ref "C11") (pin "2") (pinfunction "2_2") (pintype "passive"))
      (node (ref "C12") (pin "-") (pinfunction "-_-") (pintype "passive"))
      (node (ref "C14") (pin "2") (pinfunction "2_2") (pintype "passive"))
      (node (ref "C15") (pin "1") (pinfunction "1_1") (pintype "passive"))
      (node (ref "C16") (pin "1") (pinfunction "1_1") (pintype "passive"))
      (node (ref "C17") (pin "1") (pinfunction "1_1") (pintype "passive"))
      (node (ref "C18") (pin "1") (pinfunction "1_1") (pintype "passive"))
      (node (ref "C19") (pin "1") (pinfunction "1_1") (pintype "passive"))
      (node (ref "C2") (pin "2") (pinfunction "2_2") (pintype "passive"))
      (node (ref "C20") (pin "2") (pinfunction "2_2") (pintype "passive"))
      (node (ref "C21") (pin "2") (pinfunction "2_2") (pintype "passive"))
      (node (ref "C25") (pin "1") (pinfunction "1_1") (pintype "passive"))
      (node (ref "C26") (pin "1") (pinfunction "1_1") (pintype "passive"))
      (node (ref "C29") (pin "2") (pinfunction "2_2") (pintype "passive"))
      (node (ref "C3") (pin "2") (pinfunction "2_2") (pintype "passive"))
      (node (ref "C30") (pin "-") (pinfunction "-_-") (pintype "passive"))
      (node (ref "C4") (pin "2") (pinfunction "2_2") (pintype "passive"))
      (node (ref "C5") (pin "2") (pinfunction "2_2") (pintype "passive"))
      (node (ref "C6") (pin "2") (pinfunction "2_2") (pintype "passive"))
      (node (ref "C7") (pin "2") (pinfunction "2_2") (pintype "passive"))
      (node (ref "C8") (pin "2") (pinfunction "2_2") (pintype "passive"))
      (node (ref "CG1") (pin "2") (pinfunction "2_2") (pintype "passive"))
      (node (ref "CG2") (pin "2") (pinfunction "2_2") (pintype "passive"))
      (node (ref "CG3") (pin "2") (pinfunction "2_2") (pintype "passive"))
      (node (ref "CG4") (pin "2") (pinfunction "2_2") (pintype "passive"))
      (node (ref "CG7") (pin "2") (pinfunction "2_2") (pintype "passive"))
      (node (ref "CG8") (pin "1") (pinfunction "1_1") (pintype "passive"))
      (node (ref "COMPASS") (pin "11") (pinfunction "GND_11") (pintype "bidirectional"))
      (node (ref "COMPASS") (pin "9") (pinfunction "GND_9") (pintype "bidirectional"))
      (node (ref "HEATPAD") (pin "2") (pinfunction "S_2") (pintype "passive"))
      (node (ref "IC1") (pin "1") (pinfunction "GND_1") (pintype "power_in"))
      (node (ref "MPU-6050") (pin "1") (pinfunction "1_1") (pintype "bidirectional"))
      (node (ref "MPU-6050") (pin "11") (pinfunction "11_11") (pintype "bidirectional"))
      (node (ref "MPU-6050") (pin "18") (pinfunction "18_18") (pintype "bidirectional"))
      (node (ref "MPU-6050") (pin "9") (pinfunction "9_9") (pintype "bidirectional"))
      (node (ref "MPU-6050") (pin "P") (pinfunction "P_P") (pintype "bidirectional"))
      (node (ref "R16") (pin "1") (pinfunction "1_1") (pintype "passive"))
      (node (ref "R4") (pin "1") (pinfunction "1_1") (pintype "passive"))
      (node (ref "R5") (pin "1") (pinfunction "1_1") (pintype "passive"))
      (node (ref "R6") (pin "1") (pinfunction "1_1") (pintype "passive"))
      (node (ref "RG5") (pin "1") (pinfunction "1_1") (pintype "passive"))
      (node (ref "RSBAT") (pin "2") (pinfunction "2_2") (pintype "passive"))
      (node (ref "RVDM") (pin "1") (pinfunction "1_1") (pintype "passive"))
      (node (ref "SOLAR") (pin "1") (pinfunction "1_1") (pintype "passive"))
      (node (ref "TEMP1") (pin "1") (pinfunction "1_1") (pintype "passive"))
      (node (ref "TEMP2") (pin "2") (pinfunction "2_2") (pintype "passive"))
      (node (ref "U$1") (pin "GND") (pinfunction "GND_GND") (pintype "power_in"))
      (node (ref "U$1") (pin "GND@1") (pinfunction "GND_GND@1") (pintype "power_in"))
      (node (ref "U$1") (pin "GND@2") (pinfunction "GND_GND@2") (pintype "power_in"))
      (node (ref "U$1") (pin "GND@3") (pinfunction "GND_GND@3") (pintype "power_in"))
      (node (ref "U$1") (pin "GND@4") (pinfunction "GND_GND@4") (pintype "power_in"))
      (node (ref "U$1") (pin "GND@5") (pinfunction "GND_GND@5") (pintype "power_in"))
      (node (ref "U1") (pin "11") (pinfunction "EPAD_11") (pintype "power_in"))
      (node (ref "U1") (pin "3") (pinfunction "VSS_3") (pintype "power_in"))
      (node (ref "U2") (pin "13") (pinfunction "EPAD_13") (pintype "power_in"))
      (node (ref "U2") (pin "6") (pinfunction "VSS_6") (pintype "power_in"))
      (node (ref "U2") (pin "V") (pinfunction "EPAD1_V") (pintype "power_in"))
      (node (ref "U2") (pin "V_2") (pinfunction "EPAD2_V_2") (pintype "power_in"))
      (node (ref "U2") (pin "V_3") (pinfunction "EPAD3_V_3") (pintype "power_in"))
      (node (ref "U2") (pin "V_4") (pinfunction "EPAD4_V_4") (pintype "power_in"))
      (node (ref "U2") (pin "V_5") (pinfunction "EPAD5_V_5") (pintype "power_in"))
      (node (ref "U2") (pin "V_6") (pinfunction "EPAD6_V_6") (pintype "power_in"))
      (node (ref "U3") (pin "13") (pinfunction "EPAD_13") (pintype "passive"))
      (node (ref "U3") (pin "6") (pinfunction "GND_6") (pintype "passive"))
      (node (ref "U4") (pin "13") (pinfunction "EPAD_13") (pintype "passive"))
      (node (ref "U4") (pin "6") (pinfunction "GND_6") (pintype "passive"))
      (node (ref "U5") (pin "13") (pinfunction "EPAD_13") (pintype "passive"))
      (node (ref "U5") (pin "6") (pinfunction "GND_6") (pintype "passive"))
      (node (ref "U6") (pin "14") (pinfunction "14_14") (pintype "power_in"))
      (node (ref "U6") (pin "19") (pinfunction "19_19") (pintype "power_in"))
      (node (ref "U6") (pin "49") (pinfunction "49_49") (pintype "power_in"))
      (node (ref "U6") (pin "61") (pinfunction "61_61") (pintype "power_in"))
      (node (ref "U6") (pin "68") (pinfunction "68_68") (pintype "power_in"))
      (node (ref "U7") (pin "13") (pinfunction "EPAD_13") (pintype "passive"))
      (node (ref "U7") (pin "6") (pinfunction "GND_6") (pintype "passive"))
      (node (ref "U9") (pin "7") (pinfunction "GND_7") (pintype "power_in"))
    )
    (net (code "41") (name "M1IN1") (class "Default")
      (node (ref "U3") (pin "10") (pinfunction "AIN1_/_APHASE_10") (pintype "input"))
      (node (ref "U6") (pin "15") (pinfunction "15_15") (pintype "bidirectional"))
    )
    (net (code "42") (name "M1IN2") (class "Default")
      (node (ref "U3") (pin "9") (pinfunction "AIN2_/_AENBL_9") (pintype "input"))
      (node (ref "U6") (pin "22") (pinfunction "22_22") (pintype "bidirectional"))
    )
    (net (code "43") (name "M2IN1") (class "Default")
      (node (ref "U3") (pin "8") (pinfunction "BIN1_/_BPHASE_8") (pintype "input"))
      (node (ref "U6") (pin "16") (pinfunction "16_16") (pintype "bidirectional"))
    )
    (net (code "44") (name "M2IN2") (class "Default")
      (node (ref "U3") (pin "7") (pinfunction "BIN2_/_BENBL_7") (pintype "input"))
      (node (ref "U6") (pin "23") (pinfunction "23_23") (pintype "bidirectional"))
    )
    (net (code "45") (name "M3IN1") (class "Default")
      (node (ref "U4") (pin "10") (pinfunction "AIN1_/_APHASE_10") (pintype "input"))
      (node (ref "U6") (pin "17") (pinfunction "17_17") (pintype "bidirectional"))
    )
    (net (code "46") (name "M3IN2") (class "Default")
      (node (ref "U4") (pin "9") (pinfunction "AIN2_/_AENBL_9") (pintype "input"))
      (node (ref "U6") (pin "24") (pinfunction "24_24") (pintype "bidirectional"))
    )
    (net (code "47") (name "M4IN1") (class "Default")
      (node (ref "U4") (pin "8") (pinfunction "BIN1_/_BPHASE_8") (pintype "input"))
      (node (ref "U6") (pin "25") (pinfunction "25_25") (pintype "bidirectional"))
    )
    (net (code "48") (name "M4IN2") (class "Default")
      (node (ref "U4") (pin "7") (pinfunction "BIN2_/_BENBL_7") (pintype "input"))
      (node (ref "U6") (pin "26") (pinfunction "26_26") (pintype "bidirectional"))
    )
    (net (code "49") (name "M5IN1") (class "Default")
      (node (ref "U5") (pin "10") (pinfunction "AIN1_/_APHASE_10") (pintype "input"))
      (node (ref "U6") (pin "27") (pinfunction "27_27") (pintype "bidirectional"))
    )
    (net (code "50") (name "M5IN2") (class "Default")
      (node (ref "U5") (pin "9") (pinfunction "AIN2_/_AENBL_9") (pintype "input"))
      (node (ref "U6") (pin "28") (pinfunction "28_28") (pintype "bidirectional"))
    )
    (net (code "51") (name "M6IN1") (class "Default")
      (node (ref "U5") (pin "8") (pinfunction "BIN1_/_BPHASE_8") (pintype "input"))
      (node (ref "U6") (pin "29") (pinfunction "29_29") (pintype "bidirectional"))
    )
    (net (code "52") (name "M6IN2") (class "Default")
      (node (ref "U5") (pin "7") (pinfunction "BIN2_/_BENBL_7") (pintype "input"))
      (node (ref "U6") (pin "30") (pinfunction "30_30") (pintype "bidirectional"))
    )
    (net (code "53") (name "M7IN1") (class "Default")
      (node (ref "U6") (pin "31") (pinfunction "31_31") (pintype "bidirectional"))
      (node (ref "U7") (pin "10") (pinfunction "AIN1_/_APHASE_10") (pintype "input"))
    )
    (net (code "54") (name "M7IN2") (class "Default")
      (node (ref "U6") (pin "32") (pinfunction "32_32") (pintype "bidirectional"))
      (node (ref "U7") (pin "9") (pinfunction "AIN2_/_AENBL_9") (pintype "input"))
    )
    (net (code "55") (name "M8IN1") (class "Default")
      (node (ref "U6") (pin "33") (pinfunction "33_33") (pintype "bidirectional"))
      (node (ref "U7") (pin "8") (pinfunction "BIN1_/_BPHASE_8") (pintype "input"))
    )
    (net (code "56") (name "M8IN2") (class "Default")
      (node (ref "U6") (pin "34") (pinfunction "34_34") (pintype "bidirectional"))
      (node (ref "U7") (pin "7") (pinfunction "BIN2_/_BENBL_7") (pintype "input"))
    )
    (net (code "57") (name "M1234SLEEP") (class "Default")
      (node (ref "U3") (pin "11") (pinfunction "MODE_11") (pintype "input"))
      (node (ref "U3") (pin "12") (pinfunction "NSLEEP_12") (pintype "input"))
      (node (ref "U4") (pin "11") (pinfunction "MODE_11") (pintype "input"))
      (node (ref "U4") (pin "12") (pinfunction "NSLEEP_12") (pintype "input"))
      (node (ref "U6") (pin "21") (pinfunction "21_21") (pintype "bidirectional"))
    )
    (net (code "58") (name "M5678SLEEP") (class "Default")
      (node (ref "U5") (pin "11") (pinfunction "MODE_11") (pintype "input"))
      (node (ref "U5") (pin "12") (pinfunction "NSLEEP_12") (pintype "input"))
      (node (ref "U6") (pin "35") (pinfunction "35_35") (pintype "bidirectional"))
      (node (ref "U7") (pin "11") (pinfunction "MODE_11") (pintype "input"))
      (node (ref "U7") (pin "12") (pinfunction "NSLEEP_12") (pintype "input"))
    )
    (net (code "59") (name "Net-(C16-Pad2)") (class "Default")
      (node (ref "C16") (pin "2") (pinfunction "2_2") (pintype "passive"))
      (node (ref "MPU-6050") (pin "10") (pinfunction "10_10") (pintype "bidirectional"))
    )
    (net (code "60") (name "Net-(C18-Pad2)") (class "Default")
      (node (ref "C18") (pin "2") (pinfunction "2_2") (pintype "passive"))
      (node (ref "U6") (pin "20") (pinfunction "20_20") (pintype "power_in"))
    )
    (net (code "61") (name "Net-(C21-Pad1)") (class "Default")
      (node (ref "C21") (pin "1") (pinfunction "1_1") (pintype "passive"))
      (node (ref "MPU-6050") (pin "20") (pinfunction "20_20") (pintype "bidirectional"))
    )
    (net (code "62") (name "Net-(C25-Pad2)") (class "Default")
      (node (ref "C25") (pin "2") (pinfunction "2_2") (pintype "passive"))
      (node (ref "Q1") (pin "1") (pinfunction "1_1") (pintype "passive"))
      (node (ref "U6") (pin "13") (pinfunction "13_13") (pintype "bidirectional"))
    )
    (net (code "63") (name "Net-(C26-Pad2)") (class "Default")
      (node (ref "C26") (pin "2") (pinfunction "2_2") (pintype "passive"))
      (node (ref "Q1") (pin "2") (pinfunction "2_2") (pintype "passive"))
      (node (ref "U6") (pin "12") (pinfunction "12_12") (pintype "bidirectional"))
    )
    (net (code "64") (name "Net-(C29-Pad1)") (class "Default")
      (node (ref "C29") (pin "1") (pinfunction "1_1") (pintype "passive"))
      (node (ref "R28") (pin "1") (pinfunction "1_1") (pintype "passive"))
      (node (ref "U6") (pin "11") (pinfunction "11_11") (pintype "power_in"))
    )
    (net (code "65") (name "Net-(COMPASS-C1)") (class "Default")
      (node (ref "C10") (pin "1") (pinfunction "1_1") (pintype "passive"))
      (node (ref "COMPASS") (pin "10") (pinfunction "C1_10") (pintype "passive"))
    )
    (net (code "66") (name "Net-(COMPASS-SETC)") (class "Default")
      (node (ref "C13") (pin "1") (pinfunction "1_1") (pintype "passive"))
      (node (ref "COMPASS") (pin "12") (pinfunction "SETC_12") (pintype "passive"))
    )
    (net (code "67") (name "Net-(COMPASS-SETP)") (class "Default")
      (node (ref "C13") (pin "2") (pinfunction "2_2") (pintype "passive"))
      (node (ref "COMPASS") (pin "8") (pinfunction "SETP_8") (pintype "passive"))
    )
    (net (code "68") (name "Net-(DIGITAL2-Pad1)") (class "Default")
      (node (ref "DIGITAL2") (pin "1") (pinfunction "1_1") (pintype "passive"))
      (node (ref "U6") (pin "60") (pinfunction "60_60") (pintype "bidirectional"))
    )
    (net (code "69") (name "Net-(DIGITAL2-Pad2)") (class "Default")
      (node (ref "DIGITAL2") (pin "2") (pinfunction "2_2") (pintype "passive"))
      (node (ref "U6") (pin "59") (pinfunction "59_59") (pintype "bidirectional"))
    )
    (net (code "70") (name "Net-(DIGITAL2-Pad3)") (class "Default")
      (node (ref "DIGITAL2") (pin "3") (pinfunction "3_3") (pintype "passive"))
      (node (ref "U6") (pin "58") (pinfunction "58_58") (pintype "bidirectional"))
    )
    (net (code "71") (name "Net-(DIGITAL2-Pad4)") (class "Default")
      (node (ref "DIGITAL2") (pin "4") (pinfunction "4_4") (pintype "passive"))
      (node (ref "U6") (pin "57") (pinfunction "57_57") (pintype "bidirectional"))
    )
    (net (code "72") (name "Net-(DIGITAL2-Pad5)") (class "Default")
      (node (ref "DIGITAL2") (pin "5") (pinfunction "5_5") (pintype "passive"))
      (node (ref "U6") (pin "56") (pinfunction "56_56") (pintype "bidirectional"))
    )
    (net (code "73") (name "Net-(DIGITAL2-Pad6)") (class "Default")
      (node (ref "DIGITAL2") (pin "6") (pinfunction "6_6") (pintype "passive"))
      (node (ref "U6") (pin "55") (pinfunction "55_55") (pintype "bidirectional"))
    )
    (net (code "74") (name "Net-(DIGITAL2-Pad7)") (class "Default")
      (node (ref "DIGITAL2") (pin "7") (pinfunction "7_7") (pintype "passive"))
      (node (ref "U6") (pin "54") (pinfunction "54_54") (pintype "bidirectional"))
    )
    (net (code "75") (name "Net-(DIGITAL2-Pad8)") (class "Default")
      (node (ref "DIGITAL2") (pin "8") (pinfunction "8_8") (pintype "passive"))
      (node (ref "U6") (pin "53") (pinfunction "53_53") (pintype "bidirectional"))
    )
    (net (code "76") (name "Net-(HEATPADA-S)") (class "Default")
      (node (ref "HEATPAD") (pin "1") (pinfunction "S_1") (pintype "passive"))
      (node (ref "T1") (pin "1") (pinfunction "E_1") (pintype "passive"))
      (node (ref "T2") (pin "1") (pinfunction "E_1") (pintype "passive"))
    )
    (net (code "77") (name "Net-(L1-2)") (class "Default")
      (node (ref "L1") (pin "P$2") (pinfunction "2_P$2") (pintype "passive"))
      (node (ref "U$1") (pin "1") (pinfunction "SW_1") (pintype "input"))
      (node (ref "U$1") (pin "2") (pinfunction "SW_2") (pintype "input"))
    )
    (net (code "78") (name "Net-(LED1-PadA)") (class "Default")
      (node (ref "LED1") (pin "A") (pinfunction "A_A") (pintype "passive"))
      (node (ref "R1") (pin "1") (pinfunction "1_1") (pintype "passive"))
    )
    (net (code "79") (name "Net-(LED2-PadA)") (class "Default")
      (node (ref "LED2") (pin "A") (pinfunction "A_A") (pintype "passive"))
      (node (ref "R2") (pin "1") (pinfunction "1_1") (pintype "passive"))
    )
    (net (code "80") (name "Net-(LED3-PadC)") (class "Default")
      (node (ref "LED3") (pin "C") (pinfunction "C_C") (pintype "passive"))
      (node (ref "R6") (pin "2") (pinfunction "2_2") (pintype "passive"))
    )
    (net (code "81") (name "Net-(R16-Pad2)") (class "Default")
      (node (ref "R16") (pin "2") (pinfunction "2_2") (pintype "passive"))
      (node (ref "U6") (pin "63") (pinfunction "63_63") (pintype "bidirectional"))
    )
    (net (code "82") (name "Net-(RG2-Pad1)") (class "Default")
      (node (ref "RG2") (pin "1") (pinfunction "1_1") (pintype "passive"))
      (node (ref "RG3") (pin "2") (pinfunction "2_2") (pintype "passive"))
      (node (ref "TEMP2") (pin "1") (pinfunction "1_1") (pintype "passive"))
    )
    (net (code "83") (name "Net-(U$1-FB)") (class "Default")
      (node (ref "R3") (pin "1") (pinfunction "1_1") (pintype "passive"))
      (node (ref "R5") (pin "2") (pinfunction "2_2") (pintype "passive"))
      (node (ref "U$1") (pin "7") (pinfunction "FB_7") (pintype "input"))
    )
    (net (code "84") (name "Net-(U$1-SS)") (class "Default")
      (node (ref "C4") (pin "1") (pinfunction "1_1") (pintype "passive"))
      (node (ref "U$1") (pin "6") (pinfunction "SS_6") (pintype "input"))
    )
    (net (code "85") (name "Net-(U1-*CHG)") (class "Default")
      (node (ref "LED1") (pin "C") (pinfunction "C_C") (pintype "passive"))
      (node (ref "U1") (pin "8") (pinfunction "*CHG_8") (pintype "output"))
    )
    (net (code "86") (name "Net-(U1-*PG)") (class "Default")
      (node (ref "LED2") (pin "C") (pinfunction "C_C") (pintype "passive"))
      (node (ref "U1") (pin "6") (pinfunction "*PG_6") (pintype "output"))
    )
    (net (code "87") (name "Net-(U1-ISET)") (class "Default")
      (node (ref "R4") (pin "2") (pinfunction "2_2") (pintype "passive"))
      (node (ref "U1") (pin "2") (pinfunction "ISET_2") (pintype "input"))
    )
    (net (code "88") (name "Net-(U1-TS)") (class "Default")
      (node (ref "RT1") (pin "1") (pinfunction "1_1") (pintype "passive"))
      (node (ref "TEMP1") (pin "2") (pinfunction "2_2") (pintype "passive"))
      (node (ref "U1") (pin "5") (pinfunction "TS_5") (pintype "input"))
    )
    (net (code "89") (name "Net-(U1-VDPM)") (class "Default")
      (node (ref "RVDM") (pin "2") (pinfunction "2_2") (pintype "passive"))
      (node (ref "U1") (pin "9") (pinfunction "VDPM_9") (pintype "input"))
    )
    (net (code "90") (name "Net-(U1-VTSB)") (class "Default")
      (node (ref "RT1") (pin "2") (pinfunction "2_2") (pintype "passive"))
      (node (ref "U1") (pin "4") (pinfunction "VTSB_4") (pintype "output"))
    )
    (net (code "91") (name "Net-(U2-BI{slash}TOUT)") (class "Default")
      (node (ref "CG2") (pin "1") (pinfunction "1_1") (pintype "passive"))
      (node (ref "RG1") (pin "1") (pinfunction "1_1") (pintype "passive"))
      (node (ref "RG2") (pin "2") (pinfunction "2_2") (pintype "passive"))
      (node (ref "U2") (pin "1") (pinfunction "BI/TOUT_1") (pintype "bidirectional"))
    )
    (net (code "92") (name "Net-(U2-REG25)") (class "Default")
      (node (ref "CG4") (pin "1") (pinfunction "1_1") (pintype "passive"))
      (node (ref "RG1") (pin "2") (pinfunction "2_2") (pintype "passive"))
      (node (ref "U2") (pin "2") (pinfunction "REG25_2") (pintype "power_in"))
      (node (ref "U2") (pin "5") (pinfunction "VCC_5") (pintype "power_in"))
    )
    (net (code "93") (name "Net-(U2-SRN)") (class "Default")
      (node (ref "CG6") (pin "1") (pinfunction "1_1") (pintype "passive"))
      (node (ref "CG7") (pin "1") (pinfunction "1_1") (pintype "passive"))
      (node (ref "RG5") (pin "2") (pinfunction "2_2") (pintype "passive"))
      (node (ref "U2") (pin "8") (pinfunction "SRN_8") (pintype "input"))
    )
    (net (code "94") (name "Net-(U2-SRP)") (class "Default")
      (node (ref "CG6") (pin "2") (pinfunction "2_2") (pintype "passive"))
      (node (ref "CG8") (pin "2") (pinfunction "2_2") (pintype "passive"))
      (node (ref "RG6") (pin "2") (pinfunction "2_2") (pintype "passive"))
      (node (ref "U2") (pin "7") (pinfunction "SRP_7") (pintype "input"))
    )
    (net (code "95") (name "Net-(U2-TS)") (class "Default")
      (node (ref "CG1") (pin "1") (pinfunction "1_1") (pintype "passive"))
      (node (ref "RG3") (pin "1") (pinfunction "1_1") (pintype "passive"))
      (node (ref "U2") (pin "9") (pinfunction "TS_9") (pintype "input"))
    )
    (net (code "96") (name "Net-(U3-AOUT1)") (class "Default")
      (node (ref "SV1") (pin "1") (pinfunction "1_1") (pintype "passive"))
      (node (ref "U3") (pin "2") (pinfunction "AOUT1_2") (pintype "output"))
    )
    (net (code "97") (name "Net-(U3-AOUT2)") (class "Default")
      (node (ref "SV1") (pin "2") (pinfunction "2_2") (pintype "passive"))
      (node (ref "U3") (pin "3") (pinfunction "AOUT2_3") (pintype "output"))
    )
    (net (code "98") (name "Net-(U3-BOUT1)") (class "Default")
      (node (ref "SV1") (pin "3") (pinfunction "3_3") (pintype "passive"))
      (node (ref "U3") (pin "4") (pinfunction "BOUT1_4") (pintype "output"))
    )
    (net (code "99") (name "Net-(U3-BOUT2)") (class "Default")
      (node (ref "SV1") (pin "4") (pinfunction "4_4") (pintype "passive"))
      (node (ref "U3") (pin "5") (pinfunction "BOUT2_5") (pintype "output"))
    )
    (net (code "100") (name "Net-(U4-AOUT1)") (class "Default")
      (node (ref "SV2") (pin "1") (pinfunction "1_1") (pintype "passive"))
      (node (ref "U4") (pin "2") (pinfunction "AOUT1_2") (pintype "output"))
    )
    (net (code "101") (name "Net-(U4-AOUT2)") (class "Default")
      (node (ref "SV2") (pin "2") (pinfunction "2_2") (pintype "passive"))
      (node (ref "U4") (pin "3") (pinfunction "AOUT2_3") (pintype "output"))
    )
    (net (code "102") (name "Net-(U4-BOUT1)") (class "Default")
      (node (ref "SV2") (pin "3") (pinfunction "3_3") (pintype "passive"))
      (node (ref "U4") (pin "4") (pinfunction "BOUT1_4") (pintype "output"))
    )
    (net (code "103") (name "Net-(U4-BOUT2)") (class "Default")
      (node (ref "SV2") (pin "4") (pinfunction "4_4") (pintype "passive"))
      (node (ref "U4") (pin "5") (pinfunction "BOUT2_5") (pintype "output"))
    )
    (net (code "104") (name "Net-(U5-AOUT1)") (class "Default")
      (node (ref "SV3") (pin "1") (pinfunction "1_1") (pintype "passive"))
      (node (ref "U5") (pin "2") (pinfunction "AOUT1_2") (pintype "output"))
    )
    (net (code "105") (name "Net-(U5-AOUT2)") (class "Default")
      (node (ref "SV3") (pin "2") (pinfunction "2_2") (pintype "passive"))
      (node (ref "U5") (pin "3") (pinfunction "AOUT2_3") (pintype "output"))
    )
    (net (code "106") (name "Net-(U5-BOUT1)") (class "Default")
      (node (ref "SV3") (pin "3") (pinfunction "3_3") (pintype "passive"))
      (node (ref "U5") (pin "4") (pinfunction "BOUT1_4") (pintype "output"))
    )
    (net (code "107") (name "Net-(U5-BOUT2)") (class "Default")
      (node (ref "SV3") (pin "4") (pinfunction "4_4") (pintype "passive"))
      (node (ref "U5") (pin "5") (pinfunction "BOUT2_5") (pintype "output"))
    )
    (net (code "108") (name "Net-(U7-AOUT1)") (class "Default")
      (node (ref "SV4") (pin "1") (pinfunction "1_1") (pintype "passive"))
      (node (ref "U7") (pin "2") (pinfunction "AOUT1_2") (pintype "output"))
    )
    (net (code "109") (name "Net-(U7-AOUT2)") (class "Default")
      (node (ref "SV4") (pin "2") (pinfunction "2_2") (pintype "passive"))
      (node (ref "U7") (pin "3") (pinfunction "AOUT2_3") (pintype "output"))
    )
    (net (code "110") (name "Net-(U7-BOUT1)") (class "Default")
      (node (ref "SV4") (pin "3") (pinfunction "3_3") (pintype "passive"))
      (node (ref "U7") (pin "4") (pinfunction "BOUT1_4") (pintype "output"))
    )
    (net (code "111") (name "Net-(U7-BOUT2)") (class "Default")
      (node (ref "SV4") (pin "4") (pinfunction "4_4") (pintype "passive"))
      (node (ref "U7") (pin "5") (pinfunction "BOUT2_5") (pintype "output"))
    )
    (net (code "112") (name "VCC") (class "Default")
      (node (ref "C1") (pin "1") (pinfunction "1_1") (pintype "passive"))
      (node (ref "SOLAR") (pin "2") (pinfunction "2_2") (pintype "passive"))
      (node (ref "T1") (pin "3") (pinfunction "C_3") (pintype "passive"))
      (node (ref "U1") (pin "1") (pinfunction "VBUS_1") (pintype "bidirectional"))
    )
    (net (code "113") (name "unconnected-(COMPASS-DRDY-Pad15)") (class "Default")
      (node (ref "COMPASS") (pin "15") (pinfunction "DRDY_15") (pintype "input"))
    )
    (net (code "114") (name "unconnected-(MPU-6050-Pad6)") (class "Default")
      (node (ref "MPU-6050") (pin "6") (pinfunction "6_6") (pintype "bidirectional"))
    )
    (net (code "115") (name "unconnected-(MPU-6050-Pad7)") (class "Default")
      (node (ref "MPU-6050") (pin "7") (pinfunction "7_7") (pintype "bidirectional"))
    )
    (net (code "116") (name "unconnected-(MPU-6050-Pad12)") (class "Default")
      (node (ref "MPU-6050") (pin "12") (pinfunction "12_12") (pintype "bidirectional"))
    )
    (net (code "117") (name "unconnected-(MPU-6050-Pad22)") (class "Default")
      (node (ref "MPU-6050") (pin "22") (pinfunction "22_22") (pintype "bidirectional"))
    )
    (net (code "118") (name "unconnected-(U$1-HYS-Pad8)") (class "Default")
      (node (ref "U$1") (pin "8") (pinfunction "HYS_8") (pintype "input"))
    )
    (net (code "119") (name "unconnected-(U2-BAT_LOW{slash}BAT_GD-Pad12)") (class "Default")
      (node (ref "U2") (pin "12") (pinfunction "BAT_LOW/BAT_GD_12") (pintype "output"))
    )
    (net (code "120") (name "unconnected-(U6-Pad7)") (class "Default")
      (node (ref "U6") (pin "7") (pinfunction "7_7") (pintype "bidirectional"))
    )
    (net (code "121") (name "unconnected-(U6-Pad8)") (class "Default")
      (node (ref "U6") (pin "8") (pinfunction "8_8") (pintype "bidirectional"))
    )
    (net (code "122") (name "unconnected-(U6-Pad62)") (class "Default")
      (node (ref "U6") (pin "62") (pinfunction "62_62") (pintype "bidirectional"))
    )
    (net (code "123") (name "unconnected-(U6-Pad64)") (class "Default")
      (node (ref "U6") (pin "64") (pinfunction "64_64") (pintype "bidirectional"))
    )
    (net (code "124") (name "unconnected-(U6-Pad69)") (class "Default")
      (node (ref "U6") (pin "69") (pinfunction "69_69") (pintype "bidirectional"))
    )
    (net (code "125") (name "unconnected-(U6-Pad70)") (class "Default")
      (node (ref "U6") (pin "70") (pinfunction "70_70") (pintype "bidirectional"))
    )
    (net (code "126") (name "unconnected-(U6-Pad72)") (class "Default")
      (node (ref "U6") (pin "72") (pinfunction "72_72") (pintype "bidirectional"))
    )
    (net (code "127") (name "unconnected-(U6-Pad73)") (class "Default")
      (node (ref "U6") (pin "73") (pinfunction "73_73") (pintype "bidirectional"))
    )
    (net (code "128") (name "unconnected-(U6-Pad74)") (class "Default")
      (node (ref "U6") (pin "74") (pinfunction "74_74") (pintype "bidirectional"))
    )
    (net (code "129") (name "unconnected-(U6-Pad75)") (class "Default")
      (node (ref "U6") (pin "75") (pinfunction "75_75") (pintype "bidirectional"))
    )
  )
)
